# CC-S01-V00-Microcontroller.net
KiCad netlist of a schematic drawn in Altium Designer
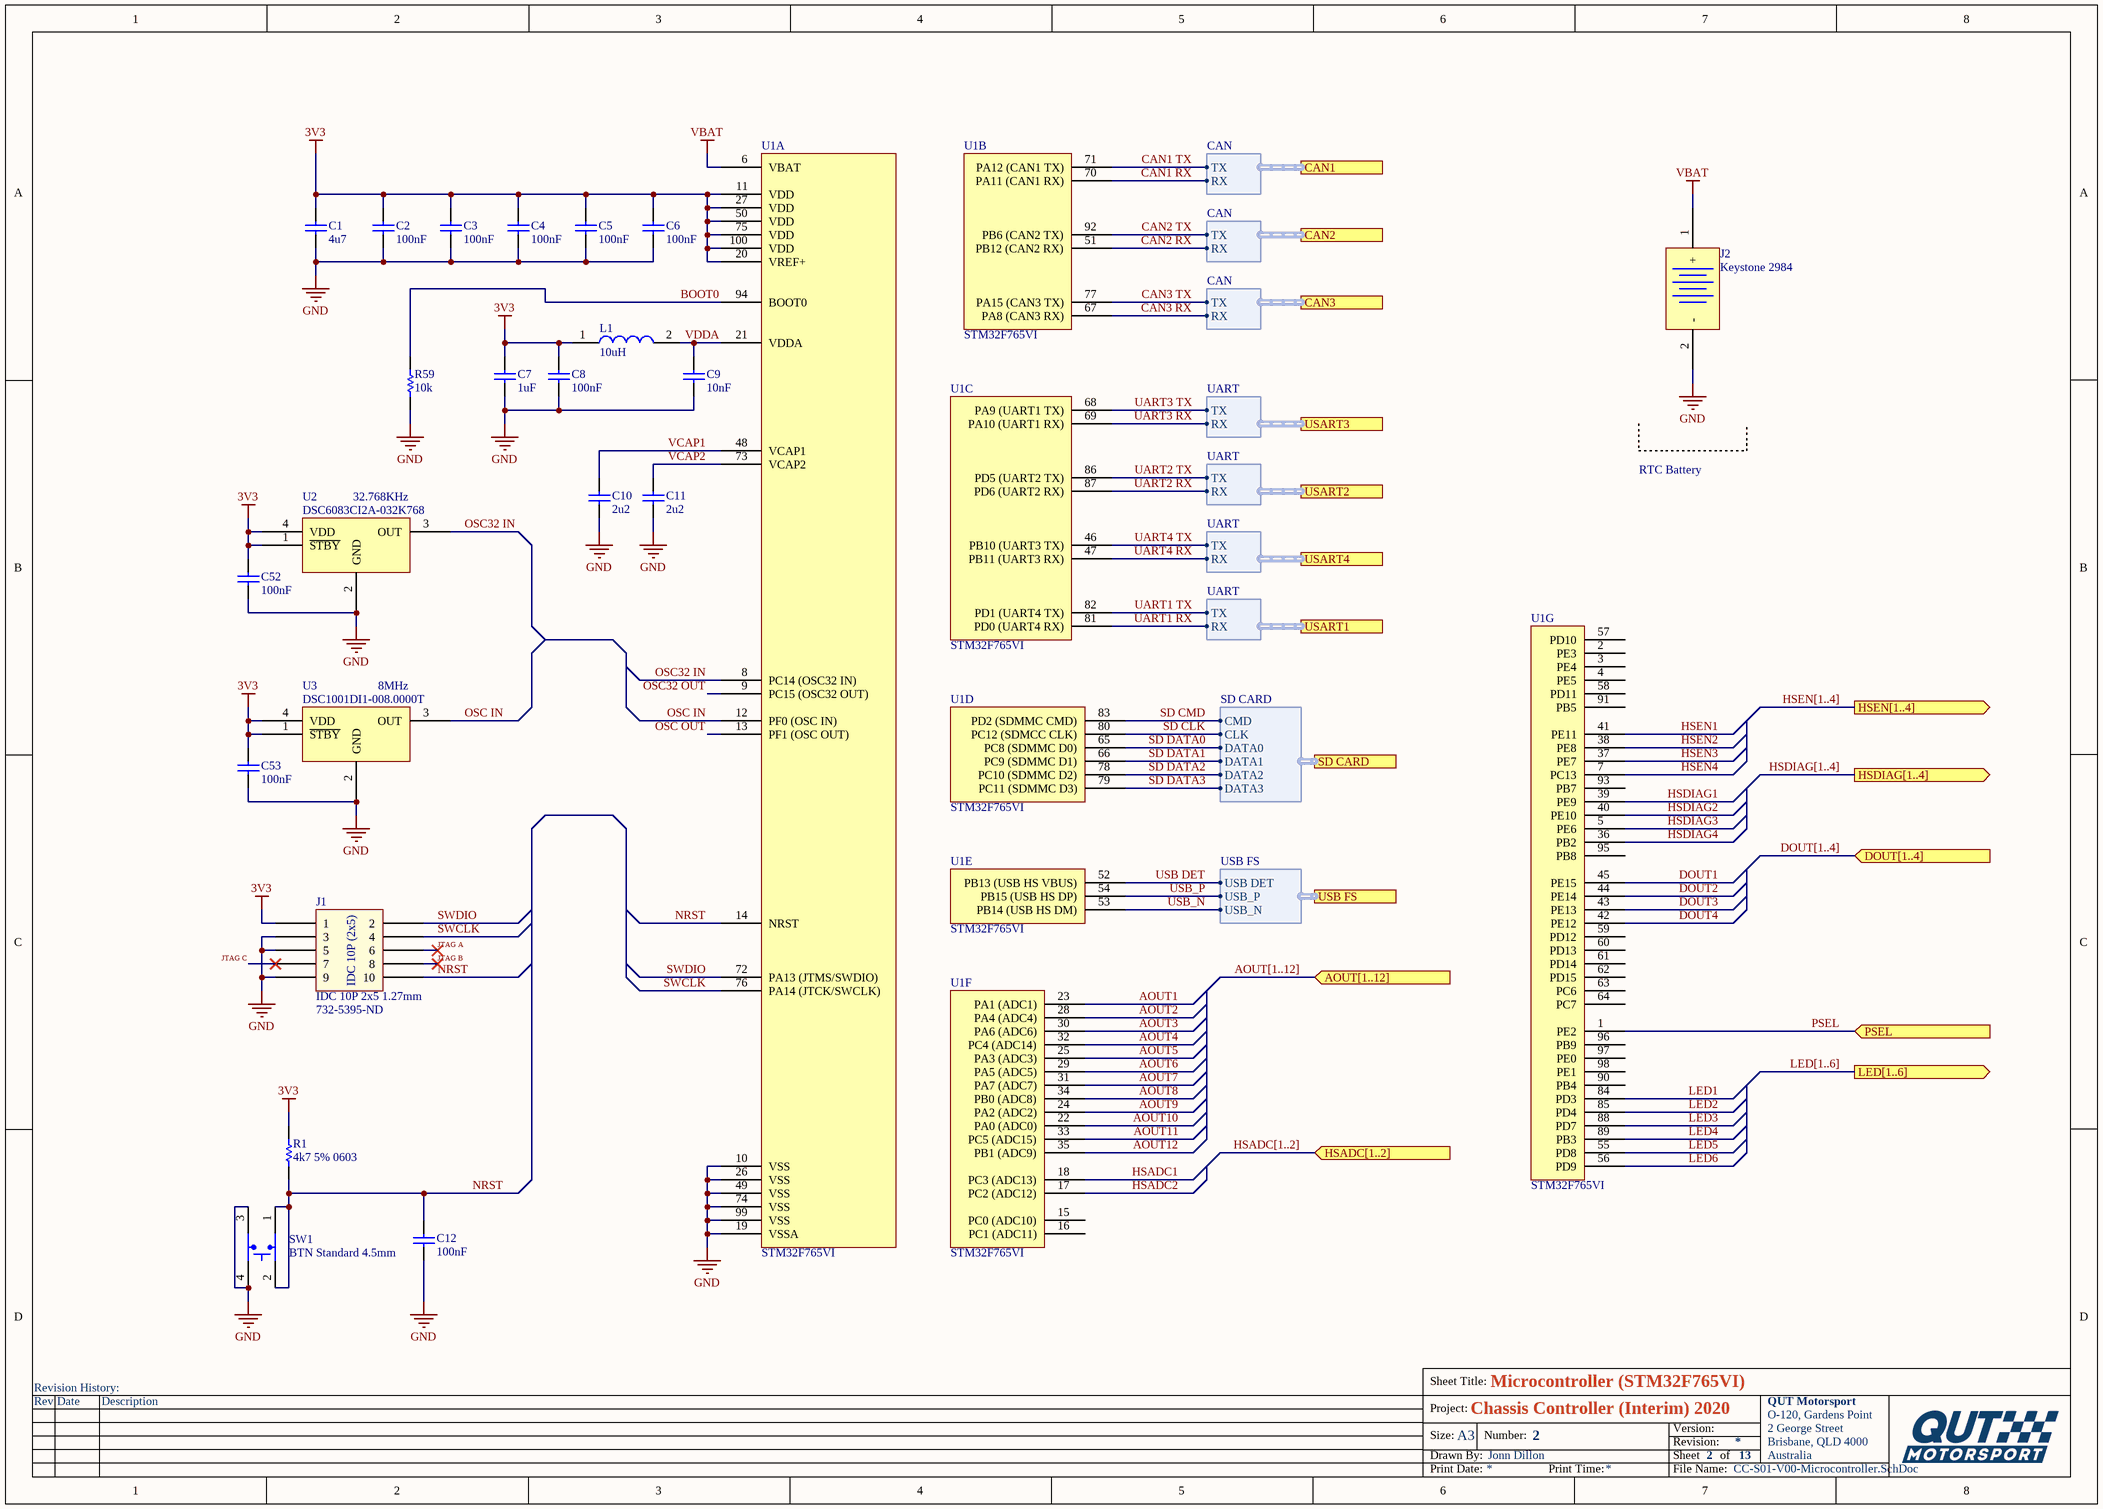
[diagram p0: CC-S01-V00-Microcontroller.SchDoc]

(export (version "E")
  (design (tool "Eeschema 10.0.6"))
  (components
    (comp (ref "C1")
      (value "4u7")
      (footprint "Cap_Ceramic_0603")
      (description "Capacitor, Ceramic, SMD, 4u7, 50V, 5%, X7R, 0603")
      (libsource (lib "StandardCapacitors") (part "4u7 50V 5% X7R 0603"))
    )
    (comp (ref "C2")
      (value "100nF")
      (footprint "Cap_Ceramic_0603")
      (description "Capacitor, Ceramic, SMD, 100nF, 50V, 5%, X7R, 0603")
      (libsource (lib "StandardCapacitors") (part "100nF 50V 5% X7R 0603"))
    )
    (comp (ref "C3")
      (value "100nF")
      (footprint "Cap_Ceramic_0603")
      (description "Capacitor, Ceramic, SMD, 100nF, 50V, 5%, X7R, 0603")
      (libsource (lib "StandardCapacitors") (part "100nF 50V 5% X7R 0603"))
    )
    (comp (ref "C4")
      (value "100nF")
      (footprint "Cap_Ceramic_0603")
      (description "Capacitor, Ceramic, SMD, 100nF, 50V, 5%, X7R, 0603")
      (libsource (lib "StandardCapacitors") (part "100nF 50V 5% X7R 0603"))
    )
    (comp (ref "C5")
      (value "100nF")
      (footprint "Cap_Ceramic_0603")
      (description "Capacitor, Ceramic, SMD, 100nF, 50V, 5%, X7R, 0603")
      (libsource (lib "StandardCapacitors") (part "100nF 50V 5% X7R 0603"))
    )
    (comp (ref "C6")
      (value "100nF")
      (footprint "Cap_Ceramic_0603")
      (description "Capacitor, Ceramic, SMD, 100nF, 50V, 5%, X7R, 0603")
      (libsource (lib "StandardCapacitors") (part "100nF 50V 5% X7R 0603"))
    )
    (comp (ref "C7")
      (value "1uF")
      (footprint "Cap_Ceramic_0603")
      (description "Capacitor, Ceramic, SMD, 1uF, 25V, 5%, X7R, 0603")
      (libsource (lib "StandardCapacitors") (part "1uF 25V 5% X7R 0603"))
    )
    (comp (ref "C8")
      (value "100nF")
      (footprint "Cap_Ceramic_0603")
      (description "Capacitor, Ceramic, SMD, 100nF, 50V, 5%, X7R, 0603")
      (libsource (lib "StandardCapacitors") (part "100nF 50V 5% X7R 0603"))
    )
    (comp (ref "C9")
      (value "10nF")
      (footprint "Cap_Ceramic_0603")
      (description "Capacitor, Ceramic, SMD, 10nF, 50V, 5%, X7R, 0603")
      (libsource (lib "StandardCapacitors") (part "10nF 50V 5% X7R 0603"))
    )
    (comp (ref "C10")
      (value "2u2")
      (footprint "Cap_Ceramic_0603")
      (description "Capacitor, Ceramic, SMD, 2u2, 25V, 5%, X7R, 0603")
      (libsource (lib "StandardCapacitors") (part "2u2 25V 5% X7R 0603"))
    )
    (comp (ref "C11")
      (value "2u2")
      (footprint "Cap_Ceramic_0603")
      (description "Capacitor, Ceramic, SMD, 2u2, 25V, 5%, X7R, 0603")
      (libsource (lib "StandardCapacitors") (part "2u2 25V 5% X7R 0603"))
    )
    (comp (ref "C12")
      (value "100nF")
      (footprint "Cap_Ceramic_0603")
      (description "Capacitor, Ceramic, SMD, 100nF, 50V, 5%, X7R, 0603")
      (libsource (lib "StandardCapacitors") (part "100nF 50V 5% X7R 0603"))
    )
    (comp (ref "C52")
      (value "100nF")
      (footprint "Cap_Ceramic_0603")
      (description "Capacitor, Ceramic, SMD, 100nF, 50V, 5%, X7R, 0603")
      (libsource (lib "StandardCapacitors") (part "100nF 50V 5% X7R 0603"))
    )
    (comp (ref "C53")
      (value "100nF")
      (footprint "Cap_Ceramic_0603")
      (description "Capacitor, Ceramic, SMD, 100nF, 50V, 5%, X7R, 0603")
      (libsource (lib "StandardCapacitors") (part "100nF 50V 5% X7R 0603"))
    )
    (comp (ref "J1")
      (value "IDC 10P 2x5 1.27mm")
      (footprint "IDC 1.27MM 10P")
      (libsource (lib "IDCConnectors") (part "IDC 10P 2x5 1.27mm"))
    )
    (comp (ref "J2")
      (value "Keystone 2984")
      (footprint "KEYSTONE 2894")
      (description "Battery Retainer Coin, 12.0mm 1 Cell SMD (SMT) Tab")
      (libsource (lib "QUTMS_BatteryLibrary") (part "Keystone 2984"))
    )
    (comp (ref "L1")
      (value "10uH")
      (footprint "Inductor_0603")
      (description "10uH, 10%, 0603")
      (libsource (lib "QUTMS_InductorLibrary") (part "10uH, 10%, 0603"))
    )
    (comp (ref "R1")
      (value "4k7 5% 0603")
      (footprint "Res_ThinFilm_0603")
      (description "Resistor, SMD, 4k7, 0.1W, 5%, 0603")
      (libsource (lib "StandardResistors") (part "4k7 5% 0603"))
    )
    (comp (ref "R59")
      (value "10k")
      (footprint "Res_ThinFilm_0603")
      (description "Resistor, SMD, 10k, 0.1W, 5%, 0603")
      (libsource (lib "StandardResistors") (part "10k 5% 0603"))
    )
    (comp (ref "SW1")
      (value "BTN Standard 4.5mm")
      (footprint "BTN STANDARD 4.5mm X 4.5mm")
      (description "Standard 4.5mm X 4.5mm momentary button")
      (libsource (lib "QUTMS_SwitchLibrary") (part "BTN Standard 4.5mm"))
    )
    (comp (ref "U1")
      (value "STM32F765VI")
      (footprint "LQFP-100")
      (description "ARM® Cortex®-M7 STM32F7 Microcontroller IC 32-Bit 216MHz 2MB (2M x 8) FLASH 100-LQFP (14x14)")
      (libsource (lib "QUTMS_STM32Library") (part "STM32F765VI"))
    )
    (comp (ref "U2")
      (value "DSC6083CI2A-032K768")
      (footprint "DSC6083CI2A-032K768")
      (description "32.768kHz XO (Standard) CMOS Oscillator 1.8V ~ 3.3V 4-SMD, No Lead")
      (libsource (lib "QUTMS_CrystalLibrary") (part "DSC6083CI2A-032K768"))
    )
    (comp (ref "U3")
      (value "DSC1001DI1-008.0000T")
      (footprint "DSC1001DI1-008.0000TCT-ND")
      (description "8MHz XO (Standard) CMOS Oscillator 1.8 ~ 3.3V Standby (Power Down) 4-SMD, No Lead")
      (libsource (lib "QUTMS_CrystalLibrary") (part "DSC1001DI1-008.0000T"))
    )
  )
  (nets
    (net (code "7") (name "/AOUT1") (class "Default")
      (node (ref "U1") (pin "23") (pinfunction "PA1_(ADC1)_23") (pintype "passive"))
    )
    (net (code "8") (name "/AOUT2") (class "Default")
      (node (ref "U1") (pin "28") (pinfunction "PA4_(ADC4)_28") (pintype "passive"))
    )
    (net (code "9") (name "/AOUT3") (class "Default")
      (node (ref "U1") (pin "30") (pinfunction "PA6_(ADC6)_30") (pintype "passive"))
    )
    (net (code "10") (name "/AOUT4") (class "Default")
      (node (ref "U1") (pin "32") (pinfunction "PC4_(ADC14)_32") (pintype "passive"))
    )
    (net (code "11") (name "/AOUT5") (class "Default")
      (node (ref "U1") (pin "25") (pinfunction "PA3_(ADC3)_25") (pintype "passive"))
    )
    (net (code "12") (name "/AOUT6") (class "Default")
      (node (ref "U1") (pin "29") (pinfunction "PA5_(ADC5)_29") (pintype "passive"))
    )
    (net (code "13") (name "/AOUT7") (class "Default")
      (node (ref "U1") (pin "31") (pinfunction "PA7_(ADC7)_31") (pintype "passive"))
    )
    (net (code "14") (name "/AOUT8") (class "Default")
      (node (ref "U1") (pin "34") (pinfunction "PB0_(ADC8)_34") (pintype "passive"))
    )
    (net (code "15") (name "/AOUT9") (class "Default")
      (node (ref "U1") (pin "24") (pinfunction "PA2_(ADC2)_24") (pintype "passive"))
    )
    (net (code "16") (name "/AOUT10") (class "Default")
      (node (ref "U1") (pin "22") (pinfunction "PA0_(ADC0)_22") (pintype "passive"))
    )
    (net (code "17") (name "/AOUT11") (class "Default")
      (node (ref "U1") (pin "33") (pinfunction "PC5_(ADC15)_33") (pintype "passive"))
    )
    (net (code "18") (name "/AOUT12") (class "Default")
      (node (ref "U1") (pin "35") (pinfunction "PB1_(ADC9)_35") (pintype "passive"))
    )
    (net (code "20") (name "/BOOT0") (class "Default")
      (node (ref "R59") (pin "2") (pinfunction "2_2") (pintype "passive"))
      (node (ref "U1") (pin "94") (pinfunction "BOOT0_94") (pintype "passive"))
    )
    (net (code "21") (name "/CAN1 RX") (class "Default")
      (node (ref "U1") (pin "70") (pinfunction "PA11_(CAN1_RX)_70") (pintype "passive"))
    )
    (net (code "22") (name "/CAN1 TX") (class "Default")
      (node (ref "U1") (pin "71") (pinfunction "PA12_(CAN1_TX)_71") (pintype "passive"))
    )
    (net (code "23") (name "/CAN2 RX") (class "Default")
      (node (ref "U1") (pin "51") (pinfunction "PB12_(CAN2_RX)_51") (pintype "passive"))
    )
    (net (code "24") (name "/CAN2 TX") (class "Default")
      (node (ref "U1") (pin "92") (pinfunction "PB6_(CAN2_TX)_92") (pintype "passive"))
    )
    (net (code "25") (name "/CAN3 RX") (class "Default")
      (node (ref "U1") (pin "67") (pinfunction "PA8_(CAN3_RX)_67") (pintype "passive"))
    )
    (net (code "26") (name "/CAN3 TX") (class "Default")
      (node (ref "U1") (pin "77") (pinfunction "PA15_(CAN3_TX)_77") (pintype "passive"))
    )
    (net (code "27") (name "/DOUT1") (class "Default")
      (node (ref "U1") (pin "45") (pinfunction "PE15_45") (pintype "passive"))
    )
    (net (code "28") (name "/DOUT2") (class "Default")
      (node (ref "U1") (pin "44") (pinfunction "PE14_44") (pintype "passive"))
    )
    (net (code "29") (name "/DOUT3") (class "Default")
      (node (ref "U1") (pin "43") (pinfunction "PE13_43") (pintype "passive"))
    )
    (net (code "30") (name "/DOUT4") (class "Default")
      (node (ref "U1") (pin "42") (pinfunction "PE12_42") (pintype "passive"))
    )
    (net (code "32") (name "/HSADC1") (class "Default")
      (node (ref "U1") (pin "18") (pinfunction "PC3_(ADC13)_18") (pintype "passive"))
    )
    (net (code "33") (name "/HSADC2") (class "Default")
      (node (ref "U1") (pin "17") (pinfunction "PC2_(ADC12)_17") (pintype "passive"))
    )
    (net (code "35") (name "/HSDIAG1") (class "Default")
      (node (ref "U1") (pin "39") (pinfunction "PE9_39") (pintype "passive"))
    )
    (net (code "36") (name "/HSDIAG2") (class "Default")
      (node (ref "U1") (pin "40") (pinfunction "PE10_40") (pintype "passive"))
    )
    (net (code "37") (name "/HSDIAG3") (class "Default")
      (node (ref "U1") (pin "5") (pinfunction "PE6_5") (pintype "passive"))
    )
    (net (code "38") (name "/HSDIAG4") (class "Default")
      (node (ref "U1") (pin "36") (pinfunction "PB2_36") (pintype "passive"))
    )
    (net (code "40") (name "/HSEN1") (class "Default")
      (node (ref "U1") (pin "41") (pinfunction "PE11_41") (pintype "passive"))
    )
    (net (code "41") (name "/HSEN2") (class "Default")
      (node (ref "U1") (pin "38") (pinfunction "PE8_38") (pintype "passive"))
    )
    (net (code "42") (name "/HSEN3") (class "Default")
      (node (ref "U1") (pin "37") (pinfunction "PE7_37") (pintype "passive"))
    )
    (net (code "43") (name "/HSEN4") (class "Default")
      (node (ref "U1") (pin "7") (pinfunction "PC13_7") (pintype "passive"))
    )
    (net (code "45") (name "/JTAG A") (class "Default")
      (node (ref "J1") (pin "6") (pinfunction "6_6") (pintype "passive+no_connect"))
    )
    (net (code "46") (name "/JTAG B") (class "Default")
      (node (ref "J1") (pin "8") (pinfunction "8_8") (pintype "passive+no_connect"))
    )
    (net (code "47") (name "/JTAG C") (class "Default")
      (node (ref "J1") (pin "7") (pinfunction "7_7") (pintype "passive+no_connect"))
    )
    (net (code "48") (name "/LED1") (class "Default")
      (node (ref "U1") (pin "84") (pinfunction "PD3_84") (pintype "passive"))
    )
    (net (code "49") (name "/LED2") (class "Default")
      (node (ref "U1") (pin "85") (pinfunction "PD4_85") (pintype "passive"))
    )
    (net (code "50") (name "/LED3") (class "Default")
      (node (ref "U1") (pin "88") (pinfunction "PD7_88") (pintype "passive"))
    )
    (net (code "51") (name "/LED4") (class "Default")
      (node (ref "U1") (pin "89") (pinfunction "PB3_89") (pintype "passive"))
    )
    (net (code "52") (name "/LED5") (class "Default")
      (node (ref "U1") (pin "55") (pinfunction "PD8_55") (pintype "passive"))
    )
    (net (code "53") (name "/LED6") (class "Default")
      (node (ref "U1") (pin "56") (pinfunction "PD9_56") (pintype "passive"))
    )
    (net (code "55") (name "/NRST") (class "Default")
      (node (ref "C12") (pin "2") (pinfunction "2_2") (pintype "passive"))
      (node (ref "J1") (pin "10") (pinfunction "10_10") (pintype "passive"))
      (node (ref "R1") (pin "1") (pinfunction "1_1") (pintype "passive"))
      (node (ref "SW1") (pin "1") (pinfunction "1_1") (pintype "passive"))
      (node (ref "SW1") (pin "2") (pinfunction "2_2") (pintype "passive"))
      (node (ref "U1") (pin "14") (pinfunction "NRST_14") (pintype "passive"))
    )
    (net (code "56") (name "/OSC IN") (class "Default")
      (node (ref "U1") (pin "12") (pinfunction "PF0_(OSC_IN)_12") (pintype "passive"))
      (node (ref "U3") (pin "3") (pinfunction "OUT_3") (pintype "passive"))
    )
    (net (code "57") (name "/OSC OUT") (class "Default")
      (node (ref "U1") (pin "13") (pinfunction "PF1_(OSC_OUT)_13") (pintype "passive"))
    )
    (net (code "58") (name "/OSC32 IN") (class "Default")
      (node (ref "U1") (pin "8") (pinfunction "PC14_(OSC32_IN)_8") (pintype "passive"))
      (node (ref "U2") (pin "3") (pinfunction "OUT_3") (pintype "passive"))
    )
    (net (code "59") (name "/OSC32 OUT") (class "Default")
      (node (ref "U1") (pin "9") (pinfunction "PC15_(OSC32_OUT)_9") (pintype "passive"))
    )
    (net (code "60") (name "/PSEL") (class "Default")
      (node (ref "U1") (pin "1") (pinfunction "PE2_1") (pintype "passive"))
    )
    (net (code "61") (name "/SD CLK") (class "Default")
      (node (ref "U1") (pin "80") (pinfunction "PC12_(SDMCC_CLK)_80") (pintype "passive"))
    )
    (net (code "62") (name "/SD CMD") (class "Default")
      (node (ref "U1") (pin "83") (pinfunction "PD2_(SDMMC_CMD)_83") (pintype "passive"))
    )
    (net (code "63") (name "/SD DATA0") (class "Default")
      (node (ref "U1") (pin "65") (pinfunction "PC8_(SDMMC_D0)_65") (pintype "passive"))
    )
    (net (code "64") (name "/SD DATA1") (class "Default")
      (node (ref "U1") (pin "66") (pinfunction "PC9_(SDMMC_D1)_66") (pintype "passive"))
    )
    (net (code "65") (name "/SD DATA2") (class "Default")
      (node (ref "U1") (pin "78") (pinfunction "PC10_(SDMMC_D2)_78") (pintype "passive"))
    )
    (net (code "66") (name "/SD DATA3") (class "Default")
      (node (ref "U1") (pin "79") (pinfunction "PC11_(SDMMC_D3)_79") (pintype "passive"))
    )
    (net (code "67") (name "/SWCLK") (class "Default")
      (node (ref "J1") (pin "4") (pinfunction "4_4") (pintype "passive"))
      (node (ref "U1") (pin "76") (pinfunction "PA14_(JTCK/SWCLK)_76") (pintype "passive"))
    )
    (net (code "68") (name "/SWDIO") (class "Default")
      (node (ref "J1") (pin "2") (pinfunction "2_2") (pintype "passive"))
      (node (ref "U1") (pin "72") (pinfunction "PA13_(JTMS/SWDIO)_72") (pintype "passive"))
    )
    (net (code "69") (name "/UART1 RX") (class "Default")
      (node (ref "U1") (pin "81") (pinfunction "PD0_(UART4_RX)_81") (pintype "passive"))
    )
    (net (code "70") (name "/UART1 TX") (class "Default")
      (node (ref "U1") (pin "82") (pinfunction "PD1_(UART4_TX)_82") (pintype "passive"))
    )
    (net (code "71") (name "/UART2 RX") (class "Default")
      (node (ref "U1") (pin "87") (pinfunction "PD6_(UART2_RX)_87") (pintype "passive"))
    )
    (net (code "72") (name "/UART2 TX") (class "Default")
      (node (ref "U1") (pin "86") (pinfunction "PD5_(UART2_TX)_86") (pintype "passive"))
    )
    (net (code "73") (name "/UART3 RX") (class "Default")
      (node (ref "U1") (pin "69") (pinfunction "PA10_(UART1_RX)_69") (pintype "passive"))
    )
    (net (code "74") (name "/UART3 TX") (class "Default")
      (node (ref "U1") (pin "68") (pinfunction "PA9_(UART1_TX)_68") (pintype "passive"))
    )
    (net (code "75") (name "/UART4 RX") (class "Default")
      (node (ref "U1") (pin "47") (pinfunction "PB11_(UART3_RX)_47") (pintype "passive"))
    )
    (net (code "76") (name "/UART4 TX") (class "Default")
      (node (ref "U1") (pin "46") (pinfunction "PB10_(UART3_TX)_46") (pintype "passive"))
    )
    (net (code "77") (name "/USB DET") (class "Default")
      (node (ref "U1") (pin "52") (pinfunction "PB13_(USB_HS_VBUS)_52") (pintype "passive"))
    )
    (net (code "78") (name "/USB_N") (class "Default")
      (node (ref "U1") (pin "53") (pinfunction "PB14_(USB_HS_DM)_53") (pintype "passive"))
    )
    (net (code "79") (name "/USB_P") (class "Default")
      (node (ref "U1") (pin "54") (pinfunction "PB15_(USB_HS_DP)_54") (pintype "passive"))
    )
    (net (code "80") (name "/VCAP1") (class "Default")
      (node (ref "C10") (pin "2") (pinfunction "2_2") (pintype "passive"))
      (node (ref "U1") (pin "48") (pinfunction "VCAP1_48") (pintype "passive"))
    )
    (net (code "81") (name "/VCAP2") (class "Default")
      (node (ref "C11") (pin "2") (pinfunction "2_2") (pintype "passive"))
      (node (ref "U1") (pin "73") (pinfunction "VCAP2_73") (pintype "passive"))
    )
    (net (code "82") (name "/VDDA") (class "Default")
      (node (ref "C9") (pin "2") (pinfunction "2_2") (pintype "passive"))
      (node (ref "L1") (pin "2") (pinfunction "2_2") (pintype "passive"))
      (node (ref "U1") (pin "21") (pinfunction "VDDA_21") (pintype "passive"))
    )
    (net (code "87") (name "3V3") (class "Default")
      (node (ref "C1") (pin "2") (pinfunction "2_2") (pintype "passive"))
      (node (ref "C2") (pin "2") (pinfunction "2_2") (pintype "passive"))
      (node (ref "C3") (pin "2") (pinfunction "2_2") (pintype "passive"))
      (node (ref "C4") (pin "2") (pinfunction "2_2") (pintype "passive"))
      (node (ref "C5") (pin "2") (pinfunction "2_2") (pintype "passive"))
      (node (ref "C52") (pin "2") (pinfunction "2_2") (pintype "passive"))
      (node (ref "C53") (pin "2") (pinfunction "2_2") (pintype "passive"))
      (node (ref "C6") (pin "2") (pinfunction "2_2") (pintype "passive"))
      (node (ref "C7") (pin "2") (pinfunction "2_2") (pintype "passive"))
      (node (ref "C8") (pin "2") (pinfunction "2_2") (pintype "passive"))
      (node (ref "J1") (pin "1") (pinfunction "1_1") (pintype "passive"))
      (node (ref "L1") (pin "1") (pinfunction "1_1") (pintype "passive"))
      (node (ref "R1") (pin "2") (pinfunction "2_2") (pintype "passive"))
      (node (ref "U1") (pin "100") (pinfunction "VDD_100") (pintype "passive"))
      (node (ref "U1") (pin "11") (pinfunction "VDD_11") (pintype "passive"))
      (node (ref "U1") (pin "20") (pinfunction "VREF+_20") (pintype "passive"))
      (node (ref "U1") (pin "27") (pinfunction "VDD_27") (pintype "passive"))
      (node (ref "U1") (pin "50") (pinfunction "VDD_50") (pintype "passive"))
      (node (ref "U1") (pin "75") (pinfunction "VDD_75") (pintype "passive"))
      (node (ref "U2") (pin "1") (pinfunction "~{STBY}_1") (pintype "passive"))
      (node (ref "U2") (pin "4") (pinfunction "VDD_4") (pintype "passive"))
      (node (ref "U3") (pin "1") (pinfunction "~{STBY}_1") (pintype "passive"))
      (node (ref "U3") (pin "4") (pinfunction "VDD_4") (pintype "passive"))
    )
    (net (code "88") (name "GND") (class "Default")
      (node (ref "C1") (pin "1") (pinfunction "1_1") (pintype "passive"))
      (node (ref "C10") (pin "1") (pinfunction "1_1") (pintype "passive"))
      (node (ref "C11") (pin "1") (pinfunction "1_1") (pintype "passive"))
      (node (ref "C12") (pin "1") (pinfunction "1_1") (pintype "passive"))
      (node (ref "C2") (pin "1") (pinfunction "1_1") (pintype "passive"))
      (node (ref "C3") (pin "1") (pinfunction "1_1") (pintype "passive"))
      (node (ref "C4") (pin "1") (pinfunction "1_1") (pintype "passive"))
      (node (ref "C5") (pin "1") (pinfunction "1_1") (pintype "passive"))
      (node (ref "C52") (pin "1") (pinfunction "1_1") (pintype "passive"))
      (node (ref "C53") (pin "1") (pinfunction "1_1") (pintype "passive"))
      (node (ref "C6") (pin "1") (pinfunction "1_1") (pintype "passive"))
      (node (ref "C7") (pin "1") (pinfunction "1_1") (pintype "passive"))
      (node (ref "C8") (pin "1") (pinfunction "1_1") (pintype "passive"))
      (node (ref "C9") (pin "1") (pinfunction "1_1") (pintype "passive"))
      (node (ref "J1") (pin "3") (pinfunction "3_3") (pintype "passive"))
      (node (ref "J1") (pin "5") (pinfunction "5_5") (pintype "passive"))
      (node (ref "J1") (pin "9") (pinfunction "9_9") (pintype "passive"))
      (node (ref "J2") (pin "2") (pinfunction "-_2") (pintype "passive"))
      (node (ref "R59") (pin "1") (pinfunction "1_1") (pintype "passive"))
      (node (ref "SW1") (pin "3") (pinfunction "3_3") (pintype "passive"))
      (node (ref "SW1") (pin "4") (pinfunction "4_4") (pintype "passive"))
      (node (ref "U1") (pin "10") (pinfunction "VSS_10") (pintype "passive"))
      (node (ref "U1") (pin "19") (pinfunction "VSSA_19") (pintype "passive"))
      (node (ref "U1") (pin "26") (pinfunction "VSS_26") (pintype "passive"))
      (node (ref "U1") (pin "49") (pinfunction "VSS_49") (pintype "passive"))
      (node (ref "U1") (pin "74") (pinfunction "VSS_74") (pintype "passive"))
      (node (ref "U1") (pin "99") (pinfunction "VSS_99") (pintype "passive"))
      (node (ref "U2") (pin "2") (pinfunction "GND_2") (pintype "passive"))
      (node (ref "U3") (pin "2") (pinfunction "GND_2") (pintype "passive"))
    )
    (net (code "89") (name "VBAT") (class "Default")
      (node (ref "J2") (pin "1") (pinfunction "+_1") (pintype "passive"))
      (node (ref "U1") (pin "6") (pinfunction "VBAT_6") (pintype "passive"))
    )
    (net (code "90") (name "unconnected-(U1F-PC0_(ADC10)-Pad15)") (class "Default")
      (node (ref "U1") (pin "15") (pinfunction "PC0_(ADC10)_15") (pintype "passive"))
    )
    (net (code "91") (name "unconnected-(U1F-PC1_(ADC11)-Pad16)") (class "Default")
      (node (ref "U1") (pin "16") (pinfunction "PC1_(ADC11)_16") (pintype "passive"))
    )
    (net (code "92") (name "unconnected-(U1G-PB4-Pad90)") (class "Default")
      (node (ref "U1") (pin "90") (pinfunction "PB4_90") (pintype "passive"))
    )
    (net (code "93") (name "unconnected-(U1G-PB5-Pad91)") (class "Default")
      (node (ref "U1") (pin "91") (pinfunction "PB5_91") (pintype "passive"))
    )
    (net (code "94") (name "unconnected-(U1G-PB7-Pad93)") (class "Default")
      (node (ref "U1") (pin "93") (pinfunction "PB7_93") (pintype "passive"))
    )
    (net (code "95") (name "unconnected-(U1G-PB8-Pad95)") (class "Default")
      (node (ref "U1") (pin "95") (pinfunction "PB8_95") (pintype "passive"))
    )
    (net (code "96") (name "unconnected-(U1G-PB9-Pad96)") (class "Default")
      (node (ref "U1") (pin "96") (pinfunction "PB9_96") (pintype "passive"))
    )
    (net (code "97") (name "unconnected-(U1G-PC6-Pad63)") (class "Default")
      (node (ref "U1") (pin "63") (pinfunction "PC6_63") (pintype "passive"))
    )
    (net (code "98") (name "unconnected-(U1G-PC7-Pad64)") (class "Default")
      (node (ref "U1") (pin "64") (pinfunction "PC7_64") (pintype "passive"))
    )
    (net (code "99") (name "unconnected-(U1G-PD10-Pad57)") (class "Default")
      (node (ref "U1") (pin "57") (pinfunction "PD10_57") (pintype "passive"))
    )
    (net (code "100") (name "unconnected-(U1G-PD11-Pad58)") (class "Default")
      (node (ref "U1") (pin "58") (pinfunction "PD11_58") (pintype "passive"))
    )
    (net (code "101") (name "unconnected-(U1G-PD12-Pad59)") (class "Default")
      (node (ref "U1") (pin "59") (pinfunction "PD12_59") (pintype "passive"))
    )
    (net (code "102") (name "unconnected-(U1G-PD13-Pad60)") (class "Default")
      (node (ref "U1") (pin "60") (pinfunction "PD13_60") (pintype "passive"))
    )
    (net (code "103") (name "unconnected-(U1G-PD14-Pad61)") (class "Default")
      (node (ref "U1") (pin "61") (pinfunction "PD14_61") (pintype "passive"))
    )
    (net (code "104") (name "unconnected-(U1G-PD15-Pad62)") (class "Default")
      (node (ref "U1") (pin "62") (pinfunction "PD15_62") (pintype "passive"))
    )
    (net (code "105") (name "unconnected-(U1G-PE0-Pad97)") (class "Default")
      (node (ref "U1") (pin "97") (pinfunction "PE0_97") (pintype "passive"))
    )
    (net (code "106") (name "unconnected-(U1G-PE1-Pad98)") (class "Default")
      (node (ref "U1") (pin "98") (pinfunction "PE1_98") (pintype "passive"))
    )
    (net (code "107") (name "unconnected-(U1G-PE3-Pad2)") (class "Default")
      (node (ref "U1") (pin "2") (pinfunction "PE3_2") (pintype "passive"))
    )
    (net (code "108") (name "unconnected-(U1G-PE4-Pad3)") (class "Default")
      (node (ref "U1") (pin "3") (pinfunction "PE4_3") (pintype "passive"))
    )
    (net (code "109") (name "unconnected-(U1G-PE5-Pad4)") (class "Default")
      (node (ref "U1") (pin "4") (pinfunction "PE5_4") (pintype "passive"))
    )
  )
)
